# SCH_Info-Portal_2024-12-21.net
KiCad netlist of a schematic drawn in EasyEDA
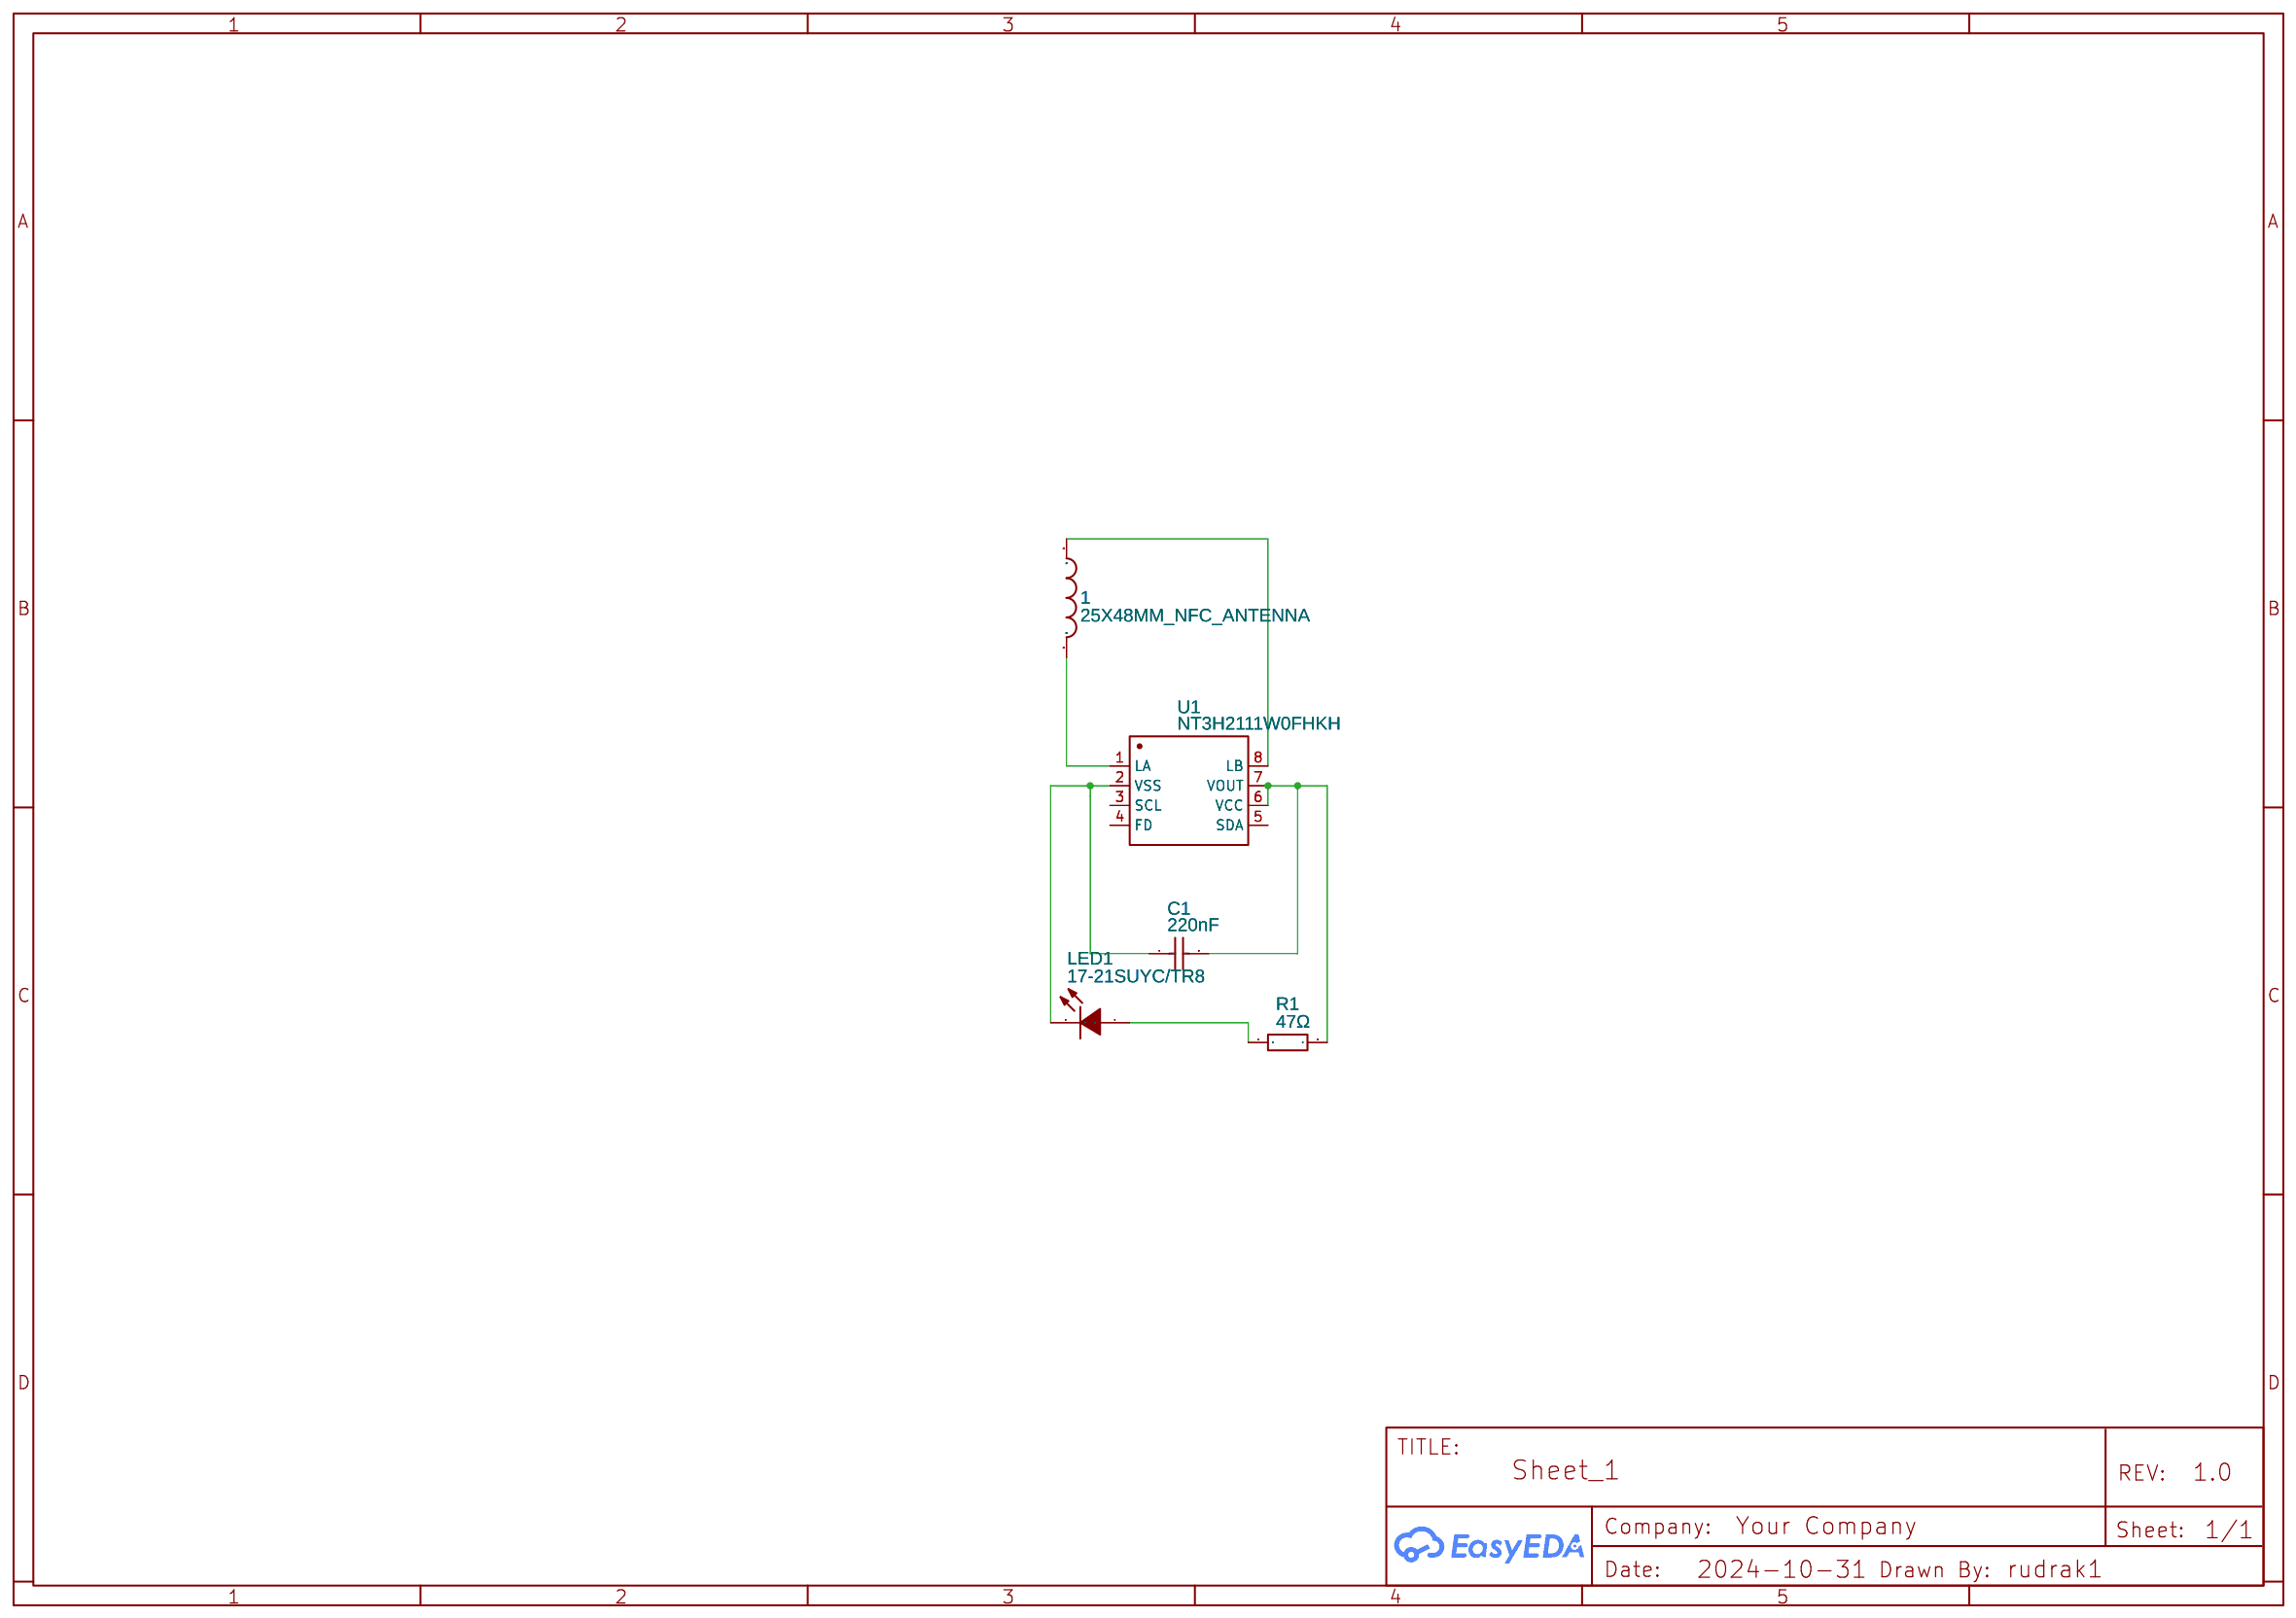
[diagram p0: schematic sheet]

(export (version "E")
  (design (tool "Eeschema 10.0.6"))
  (components
    (comp (ref "1") (value "25X48MM_NFC_ANTENNA") (libsource (lib "") (part "25X48MM_NFC_ANTENNA")))
    (comp (ref "C1")
      (value "220nF")
      (fields
        (field (name "Manufacturer Part") "CL10B224KA8NNNC")
        (field (name "Manufacturer") "SAMSUNG(三星)")
      )
      (libsource (lib "") (part "CL10B224KA8NNNC"))
    )
    (comp (ref "LED1")
      (value "17-21SUYC/TR8")
      (fields (field (name "Manufacturer Part") "KT-0805黄灯") (field (name "Manufacturer") "KENTO"))
      (libsource (lib "") (part "17-21SUYC/TR8"))
    )
    (comp (ref "R1")
      (value "47Ω")
      (fields
        (field (name "Manufacturer Part") "0603WAF470JT5E")
        (field (name "Manufacturer") "UNI-ROYAL(厚声)")
      )
      (libsource (lib "") (part "0603WAF470JT5E"))
    )
    (comp (ref "U1")
      (value "NT3H2111W0FHKH")
      (fields (field (name "Manufacturer") "NXP(恩智浦)"))
      (libsource (lib "") (part "NT3H2111W0FHKH"))
    )
  )
  (nets
    (net (code "1") (name "Net-(LED1-+)") (class "Default")
      (node (ref "LED1") (pin "1") (pinfunction "+_1") (pintype "unspecified"))
      (node (ref "R1") (pin "1") (pinfunction "1_1") (pintype "input"))
    )
    (net (code "2") (name "Net-(LED1--)") (class "Default")
      (node (ref "C1") (pin "1") (pinfunction "1_1") (pintype "input"))
      (node (ref "LED1") (pin "2") (pinfunction "-_2") (pintype "unspecified"))
      (node (ref "U1") (pin "2") (pinfunction "VSS_2") (pintype "unspecified"))
    )
    (net (code "3") (name "Net-(U1-LA)") (class "Default")
      (node (ref "1") (pin "P$2") (pinfunction "P$2_P$2") (pintype "bidirectional"))
      (node (ref "U1") (pin "1") (pinfunction "LA_1") (pintype "unspecified"))
    )
    (net (code "4") (name "Net-(U1-LB)") (class "Default")
      (node (ref "1") (pin "P$1") (pinfunction "P$1_P$1") (pintype "bidirectional"))
      (node (ref "U1") (pin "8") (pinfunction "LB_8") (pintype "unspecified"))
    )
    (net (code "5") (name "Net-(U1-VCC)") (class "Default")
      (node (ref "C1") (pin "2") (pinfunction "2_2") (pintype "input"))
      (node (ref "R1") (pin "2") (pinfunction "2_2") (pintype "input"))
      (node (ref "U1") (pin "6") (pinfunction "VCC_6") (pintype "unspecified"))
      (node (ref "U1") (pin "7") (pinfunction "VOUT_7") (pintype "unspecified"))
    )
    (net (code "6") (name "unconnected-(U1-FD-Pad4)") (class "Default")
      (node (ref "U1") (pin "4") (pinfunction "FD_4") (pintype "unspecified"))
    )
    (net (code "7") (name "unconnected-(U1-SCL-Pad3)") (class "Default")
      (node (ref "U1") (pin "3") (pinfunction "SCL_3") (pintype "unspecified"))
    )
    (net (code "8") (name "unconnected-(U1-SDA-Pad5)") (class "Default")
      (node (ref "U1") (pin "5") (pinfunction "SDA_5") (pintype "unspecified"))
    )
  )
)
